# 1602.net
KiCad netlist of a schematic drawn in Altium Designer
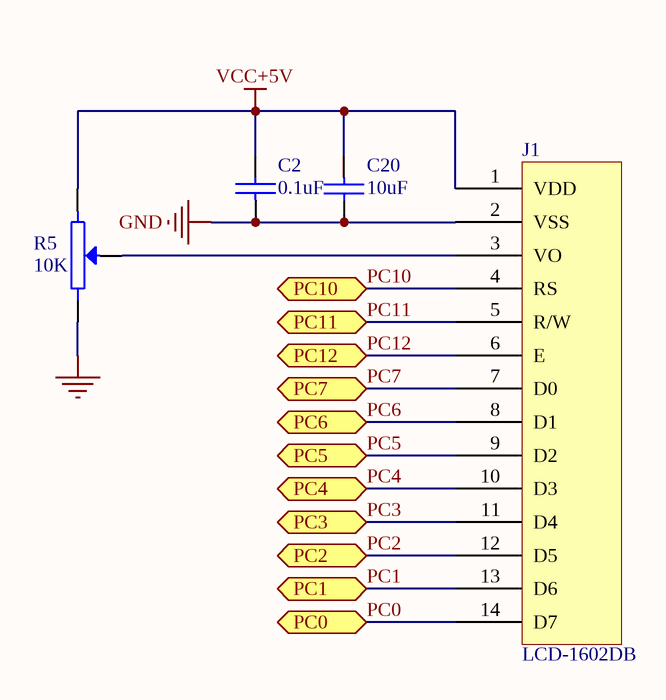
[diagram p0: 1602液晶屏.SchDoc]

(export (version "E")
  (design (tool "Eeschema 10.0.6"))
  (components
    (comp (ref "C2")
      (value "0.1uF")
      (footprint "0603")
      (description "0603陶瓷贴片电容")
      (libsource (lib "INSPUR_PCB") (part "CAP-0603"))
    )
    (comp (ref "C20")
      (value "10uF")
      (footprint "0805")
      (description "0805陶瓷贴片电容")
      (libsource (lib "INSPUR_PCB") (part "CAP-0805"))
    )
    (comp (ref "J1")
      (value "LCD-1602DB")
      (footprint "LCD-1602B")
      (libsource (lib "INSPUR_PCB") (part "LCD-1602DB"))
    )
    (comp (ref "R5")
      (value "10K")
      (footprint "RM065-V1")
      (description "三端可调电位器10K")
      (libsource (lib "INSPUR_SCH") (part "POT2"))
    )
  )
  (nets
    (net (code "1") (name "/PC0") (class "Default")
      (node (ref "J1") (pin "14") (pinfunction "D7_14") (pintype "passive"))
    )
    (net (code "2") (name "/PC1") (class "Default")
      (node (ref "J1") (pin "13") (pinfunction "D6_13") (pintype "passive"))
    )
    (net (code "3") (name "/PC2") (class "Default")
      (node (ref "J1") (pin "12") (pinfunction "D5_12") (pintype "passive"))
    )
    (net (code "4") (name "/PC3") (class "Default")
      (node (ref "J1") (pin "11") (pinfunction "D4_11") (pintype "passive"))
    )
    (net (code "5") (name "/PC4") (class "Default")
      (node (ref "J1") (pin "10") (pinfunction "D3_10") (pintype "passive"))
    )
    (net (code "6") (name "/PC5") (class "Default")
      (node (ref "J1") (pin "9") (pinfunction "D2_9") (pintype "passive"))
    )
    (net (code "7") (name "/PC6") (class "Default")
      (node (ref "J1") (pin "8") (pinfunction "D1_8") (pintype "passive"))
    )
    (net (code "8") (name "/PC7") (class "Default")
      (node (ref "J1") (pin "7") (pinfunction "D0_7") (pintype "passive"))
    )
    (net (code "9") (name "/PC10") (class "Default")
      (node (ref "J1") (pin "4") (pinfunction "RS_4") (pintype "passive"))
    )
    (net (code "10") (name "/PC11") (class "Default")
      (node (ref "J1") (pin "5") (pinfunction "R/W_5") (pintype "passive"))
    )
    (net (code "11") (name "/PC12") (class "Default")
      (node (ref "J1") (pin "6") (pinfunction "E_6") (pintype "passive"))
    )
    (net (code "12") (name "GND") (class "Default")
      (node (ref "C2") (pin "1") (pinfunction "1_1") (pintype "passive"))
      (node (ref "C20") (pin "2") (pinfunction "2_2") (pintype "passive"))
      (node (ref "J1") (pin "2") (pinfunction "VSS_2") (pintype "passive"))
      (node (ref "R5") (pin "3") (pinfunction "3_3") (pintype "passive"))
    )
    (net (code "13") (name "Net-(J1-VO)") (class "Default")
      (node (ref "J1") (pin "3") (pinfunction "VO_3") (pintype "passive"))
      (node (ref "R5") (pin "2") (pinfunction "2_2") (pintype "passive"))
    )
    (net (code "14") (name "VCC+5V") (class "Default")
      (node (ref "C2") (pin "2") (pinfunction "2_2") (pintype "passive"))
      (node (ref "C20") (pin "1") (pinfunction "1_1") (pintype "passive"))
      (node (ref "J1") (pin "1") (pinfunction "VDD_1") (pintype "passive"))
      (node (ref "R5") (pin "1") (pinfunction "1_1") (pintype "passive"))
    )
  )
)
